# Sheet1.net
KiCad netlist of a schematic drawn in Altium Designer
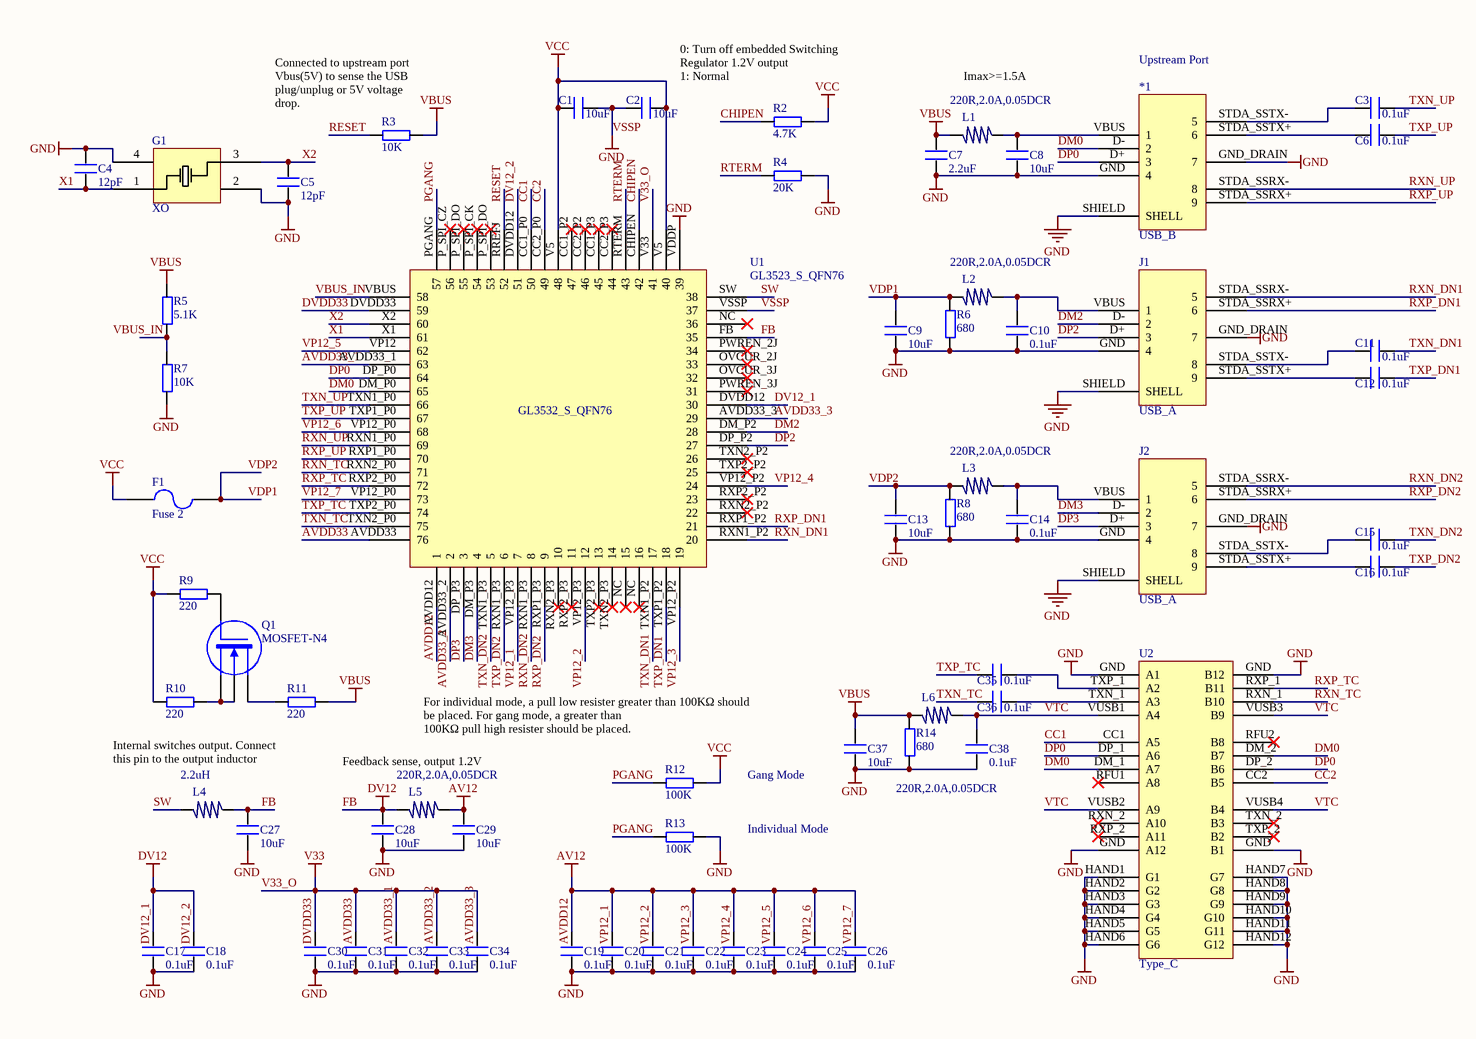
[diagram p0: Sheet1.SchDoc]

(export (version "E")
  (design (tool "Eeschema 10.0.6"))
  (components
    (comp (ref "*1") (value "USB_B") (libsource (lib "GL3532") (part "USB_B")))
    (comp (ref "C1") (value "10uF") (footprint "0603P") (libsource (lib "Explorer STM32F407封装库") (part "C")))
    (comp (ref "C2") (value "10uF") (footprint "0603P") (libsource (lib "Explorer STM32F407封装库") (part "C")))
    (comp (ref "C3") (value "0.1uF") (footprint "0603P") (libsource (lib "Explorer STM32F407封装库") (part "C")))
    (comp (ref "C4") (value "12pF") (footprint "0603P") (libsource (lib "Explorer STM32F407封装库") (part "C")))
    (comp (ref "C5") (value "12pF") (footprint "0603P") (libsource (lib "Explorer STM32F407封装库") (part "C")))
    (comp (ref "C6") (value "0.1uF") (footprint "0603P") (libsource (lib "Explorer STM32F407封装库") (part "C")))
    (comp (ref "C7") (value "2.2uF") (footprint "0603P") (libsource (lib "Explorer STM32F407封装库") (part "C")))
    (comp (ref "C8") (value "10uF") (footprint "0603P") (libsource (lib "Explorer STM32F407封装库") (part "C")))
    (comp (ref "C9") (value "10uF") (footprint "0603P") (libsource (lib "Explorer STM32F407封装库") (part "C")))
    (comp (ref "C10")
      (value "0.1uF")
      (footprint "0603P")
      (libsource (lib "Explorer STM32F407封装库") (part "C"))
    )
    (comp (ref "C11")
      (value "0.1uF")
      (footprint "0603P")
      (libsource (lib "Explorer STM32F407封装库") (part "C"))
    )
    (comp (ref "C12")
      (value "0.1uF")
      (footprint "0603P")
      (libsource (lib "Explorer STM32F407封装库") (part "C"))
    )
    (comp (ref "C13") (value "10uF") (footprint "0603P") (libsource (lib "Explorer STM32F407封装库") (part "C")))
    (comp (ref "C14")
      (value "0.1uF")
      (footprint "0603P")
      (libsource (lib "Explorer STM32F407封装库") (part "C"))
    )
    (comp (ref "C15")
      (value "0.1uF")
      (footprint "0603P")
      (libsource (lib "Explorer STM32F407封装库") (part "C"))
    )
    (comp (ref "C16")
      (value "0.1uF")
      (footprint "0603P")
      (libsource (lib "Explorer STM32F407封装库") (part "C"))
    )
    (comp (ref "C17")
      (value "0.1uF")
      (footprint "0603P")
      (libsource (lib "Explorer STM32F407封装库") (part "C"))
    )
    (comp (ref "C18")
      (value "0.1uF")
      (footprint "0603P")
      (libsource (lib "Explorer STM32F407封装库") (part "C"))
    )
    (comp (ref "C19")
      (value "0.1uF")
      (footprint "0603P")
      (libsource (lib "Explorer STM32F407封装库") (part "C"))
    )
    (comp (ref "C20")
      (value "0.1uF")
      (footprint "0603P")
      (libsource (lib "Explorer STM32F407封装库") (part "C"))
    )
    (comp (ref "C21")
      (value "0.1uF")
      (footprint "0603P")
      (libsource (lib "Explorer STM32F407封装库") (part "C"))
    )
    (comp (ref "C22")
      (value "0.1uF")
      (footprint "0603P")
      (libsource (lib "Explorer STM32F407封装库") (part "C"))
    )
    (comp (ref "C23")
      (value "0.1uF")
      (footprint "0603P")
      (libsource (lib "Explorer STM32F407封装库") (part "C"))
    )
    (comp (ref "C24")
      (value "0.1uF")
      (footprint "0603P")
      (libsource (lib "Explorer STM32F407封装库") (part "C"))
    )
    (comp (ref "C25")
      (value "0.1uF")
      (footprint "0603P")
      (libsource (lib "Explorer STM32F407封装库") (part "C"))
    )
    (comp (ref "C26")
      (value "0.1uF")
      (footprint "0603P")
      (libsource (lib "Explorer STM32F407封装库") (part "C"))
    )
    (comp (ref "C27") (value "10uF") (footprint "0603P") (libsource (lib "Explorer STM32F407封装库") (part "C")))
    (comp (ref "C28") (value "10uF") (footprint "0603P") (libsource (lib "Explorer STM32F407封装库") (part "C")))
    (comp (ref "C29") (value "10uF") (footprint "0603P") (libsource (lib "Explorer STM32F407封装库") (part "C")))
    (comp (ref "C30")
      (value "0.1uF")
      (footprint "0603P")
      (libsource (lib "Explorer STM32F407封装库") (part "C"))
    )
    (comp (ref "C31")
      (value "0.1uF")
      (footprint "0603P")
      (libsource (lib "Explorer STM32F407封装库") (part "C"))
    )
    (comp (ref "C32")
      (value "0.1uF")
      (footprint "0603P")
      (libsource (lib "Explorer STM32F407封装库") (part "C"))
    )
    (comp (ref "C33")
      (value "0.1uF")
      (footprint "0603P")
      (libsource (lib "Explorer STM32F407封装库") (part "C"))
    )
    (comp (ref "C34")
      (value "0.1uF")
      (footprint "0603P")
      (libsource (lib "Explorer STM32F407封装库") (part "C"))
    )
    (comp (ref "C35")
      (value "0.1uF")
      (footprint "0603P")
      (libsource (lib "Explorer STM32F407封装库") (part "C"))
    )
    (comp (ref "C36")
      (value "0.1uF")
      (footprint "0603P")
      (libsource (lib "Explorer STM32F407封装库") (part "C"))
    )
    (comp (ref "C37") (value "10uF") (footprint "0603P") (libsource (lib "Explorer STM32F407封装库") (part "C")))
    (comp (ref "C38")
      (value "0.1uF")
      (footprint "0603P")
      (libsource (lib "Explorer STM32F407封装库") (part "C"))
    )
    (comp (ref "F1")
      (value "Fuse 2")
      (footprint "PIN-W2/E2.8")
      (description "Fuse")
      (fields (field (name "PUBLISHER") "Altium Limited"))
      (libsource (lib "Miscellaneous Devices") (part "Fuse 2"))
    )
    (comp (ref "G1") (value "XO") (description "25M XO") (libsource (lib "GL3532") (part "XO")))
    (comp (ref "J1") (value "USB_A") (description "USB3.0-A") (libsource (lib "GL3532") (part "USB_A")))
    (comp (ref "J2") (value "USB_A") (description "USB3.0-A") (libsource (lib "GL3532") (part "USB_A")))
    (comp (ref "L1")
      (value "220R,2.0A,0.05DCR")
      (footprint "0603P")
      (libsource (lib "Explorer STM32F407封装库") (part "L"))
    )
    (comp (ref "L2")
      (value "220R,2.0A,0.05DCR")
      (footprint "0603P")
      (libsource (lib "Explorer STM32F407封装库") (part "L"))
    )
    (comp (ref "L3")
      (value "220R,2.0A,0.05DCR")
      (footprint "0603P")
      (libsource (lib "Explorer STM32F407封装库") (part "L"))
    )
    (comp (ref "L4") (value "2.2uH") (footprint "0603P") (libsource (lib "Explorer STM32F407封装库") (part "L")))
    (comp (ref "L5")
      (value "220R,2.0A,0.05DCR")
      (footprint "0603P")
      (libsource (lib "Explorer STM32F407封装库") (part "L"))
    )
    (comp (ref "L6")
      (value "220R,2.0A,0.05DCR")
      (footprint "0603P")
      (libsource (lib "Explorer STM32F407封装库") (part "L"))
    )
    (comp (ref "Q1")
      (value "MOSFET-N4")
      (footprint "SOT-343_N")
      (description "N-Channel MOSFET, Externally Terminated Substrate")
      (fields (field (name "PUBLISHER") "Altium Limited"))
      (libsource (lib "Miscellaneous Devices") (part "MOSFET-N4"))
    )
    (comp (ref "R2") (value "4.7K") (footprint "0603P") (libsource (lib "Explorer STM32F407封装库") (part "R")))
    (comp (ref "R3") (value "10K") (footprint "0603P") (libsource (lib "Explorer STM32F407封装库") (part "R")))
    (comp (ref "R4") (value "20K") (footprint "0603P") (libsource (lib "Explorer STM32F407封装库") (part "R")))
    (comp (ref "R5") (value "5.1K") (footprint "0603P") (libsource (lib "Explorer STM32F407封装库") (part "R")))
    (comp (ref "R6") (value "680") (footprint "0603P") (libsource (lib "Explorer STM32F407封装库") (part "R")))
    (comp (ref "R7") (value "10K") (footprint "0603P") (libsource (lib "Explorer STM32F407封装库") (part "R")))
    (comp (ref "R8") (value "680") (footprint "0603P") (libsource (lib "Explorer STM32F407封装库") (part "R")))
    (comp (ref "R9") (value "220") (footprint "0603P") (libsource (lib "Explorer STM32F407封装库") (part "R")))
    (comp (ref "R10") (value "220") (footprint "0603P") (libsource (lib "Explorer STM32F407封装库") (part "R")))
    (comp (ref "R11") (value "220") (footprint "0603P") (libsource (lib "Explorer STM32F407封装库") (part "R")))
    (comp (ref "R12") (value "100K") (footprint "0603P") (libsource (lib "Explorer STM32F407封装库") (part "R")))
    (comp (ref "R13") (value "100K") (footprint "0603P") (libsource (lib "Explorer STM32F407封装库") (part "R")))
    (comp (ref "R14") (value "680") (footprint "0603P") (libsource (lib "Explorer STM32F407封装库") (part "R")))
    (comp (ref "U1") (value "GL3523_S_QFN76") (libsource (lib "GL3532") (part "GL3523_S_QFN76")))
    (comp (ref "U2") (value "Type_C") (libsource (lib "GL3532") (part "Type_C")))
  )
  (nets
    (net (code "1") (name "/AVDD12") (class "Default")
      (node (ref "U1") (pin "AVDD12") (pinfunction "1_AVDD12") (pintype "passive"))
    )
    (net (code "2") (name "/AVDD33") (class "Default")
      (node (ref "U1") (pin "AVDD33") (pinfunction "76_AVDD33") (pintype "passive"))
    )
    (net (code "3") (name "/AVDD33_1") (class "Default")
      (node (ref "U1") (pin "AVDD33_1") (pinfunction "63_AVDD33_1") (pintype "passive"))
    )
    (net (code "5") (name "/AVDD33_3") (class "Default")
      (node (ref "U1") (pin "AVDD33_3") (pinfunction "29_AVDD33_3") (pintype "passive"))
    )
    (net (code "6") (name "/CC1") (class "Default")
      (node (ref "U1") (pin "CC1_P0") (pinfunction "50_CC1_P0") (pintype "passive"))
      (node (ref "U2") (pin "CC1") (pinfunction "A5_CC1") (pintype "passive"))
    )
    (net (code "7") (name "/CC2") (class "Default")
      (node (ref "U1") (pin "CC2_P0") (pinfunction "49_CC2_P0") (pintype "passive"))
      (node (ref "U2") (pin "CC2") (pinfunction "B5_CC2") (pintype "passive"))
    )
    (net (code "8") (name "/CHIPEN") (class "Default")
      (node (ref "R2") (pin "1") (pintype "passive"))
      (node (ref "U1") (pin "CHIPEN") (pinfunction "42_CHIPEN") (pintype "passive"))
    )
    (net (code "9") (name "/DM0") (class "Default")
      (node (ref "*1") (pin "D-") (pinfunction "2_D-") (pintype "passive"))
      (node (ref "U1") (pin "DM_P0") (pinfunction "65_DM_P0") (pintype "passive"))
      (node (ref "U2") (pin "DM_1") (pinfunction "A7_DM_1") (pintype "passive"))
      (node (ref "U2") (pin "DM_2") (pinfunction "B7_DM_2") (pintype "passive"))
    )
    (net (code "10") (name "/DM2") (class "Default")
      (node (ref "J1") (pin "D-") (pinfunction "2_D-") (pintype "passive"))
      (node (ref "U1") (pin "DM_P2") (pinfunction "28_DM_P2") (pintype "passive"))
    )
    (net (code "11") (name "/DM3") (class "Default")
      (node (ref "J2") (pin "D-") (pinfunction "2_D-") (pintype "passive"))
      (node (ref "U1") (pin "DM_P3") (pinfunction "4_DM_P3") (pintype "passive"))
    )
    (net (code "12") (name "/DP0") (class "Default")
      (node (ref "*1") (pin "D+") (pinfunction "3_D+") (pintype "passive"))
      (node (ref "U1") (pin "DP_P0") (pinfunction "64_DP_P0") (pintype "passive"))
      (node (ref "U2") (pin "DP_1") (pinfunction "A6_DP_1") (pintype "passive"))
      (node (ref "U2") (pin "DP_2") (pinfunction "B6_DP_2") (pintype "passive"))
    )
    (net (code "13") (name "/DP2") (class "Default")
      (node (ref "J1") (pin "D+") (pinfunction "3_D+") (pintype "passive"))
      (node (ref "U1") (pin "DP_P2") (pinfunction "27_DP_P2") (pintype "passive"))
    )
    (net (code "14") (name "/DP3") (class "Default")
      (node (ref "J2") (pin "D+") (pinfunction "3_D+") (pintype "passive"))
      (node (ref "U1") (pin "DP_P3") (pinfunction "3_DP_P3") (pintype "passive"))
    )
    (net (code "15") (name "/DV12_1") (class "Default")
      (node (ref "U1") (pin "DVDD12") (pinfunction "30_DVDD12") (pintype "passive"))
    )
    (net (code "16") (name "/DV12_2") (class "Default")
      (node (ref "U1") (pin "DVDD12") (pinfunction "51_DVDD12") (pintype "passive"))
    )
    (net (code "17") (name "/DVDD33") (class "Default")
      (node (ref "U1") (pin "DVDD33") (pinfunction "59_DVDD33") (pintype "passive"))
    )
    (net (code "18") (name "/PGANG") (class "Default")
      (node (ref "R12") (pin "1") (pintype "passive"))
      (node (ref "R13") (pin "1") (pintype "passive"))
      (node (ref "U1") (pin "PGANG") (pinfunction "57_PGANG") (pintype "passive"))
    )
    (net (code "19") (name "/RESET") (class "Default")
      (node (ref "R3") (pin "1") (pintype "passive"))
      (node (ref "U1") (pin "RREFJ") (pinfunction "52_RREFJ") (pintype "passive"))
    )
    (net (code "20") (name "/RTERM") (class "Default")
      (node (ref "R4") (pin "1") (pintype "passive"))
      (node (ref "U1") (pin "RTERM") (pinfunction "43_RTERM") (pintype "passive"))
    )
    (net (code "21") (name "/RXN_DN1") (class "Default")
      (node (ref "J1") (pin "STDA_SSRX-") (pinfunction "5_STDA_SSRX-") (pintype "passive"))
      (node (ref "U1") (pin "RXN1_P2") (pinfunction "20_RXN1_P2") (pintype "passive"))
    )
    (net (code "22") (name "/RXN_DN2") (class "Default")
      (node (ref "J2") (pin "STDA_SSRX-") (pinfunction "5_STDA_SSRX-") (pintype "passive"))
    )
    (net (code "23") (name "/RXN_TC") (class "Default")
      (node (ref "U1") (pin "RXN2_P0") (pinfunction "71_RXN2_P0") (pintype "passive"))
      (node (ref "U2") (pin "RXN_1") (pinfunction "B10_RXN_1") (pintype "passive"))
    )
    (net (code "24") (name "/RXN_UP") (class "Default")
      (node (ref "*1") (pin "STDA_SSRX-") (pinfunction "8_STDA_SSRX-") (pintype "passive"))
      (node (ref "U1") (pin "RXN1_P0") (pinfunction "69_RXN1_P0") (pintype "passive"))
    )
    (net (code "25") (name "/RXP_DN1") (class "Default")
      (node (ref "J1") (pin "STDA_SSRX+") (pinfunction "6_STDA_SSRX+") (pintype "passive"))
      (node (ref "U1") (pin "RXP1_P2") (pinfunction "21_RXP1_P2") (pintype "passive"))
    )
    (net (code "26") (name "/RXP_DN2") (class "Default")
      (node (ref "J2") (pin "STDA_SSRX+") (pinfunction "6_STDA_SSRX+") (pintype "passive"))
    )
    (net (code "27") (name "/RXP_TC") (class "Default")
      (node (ref "U1") (pin "RXP2_P0") (pinfunction "72_RXP2_P0") (pintype "passive"))
      (node (ref "U2") (pin "RXP_1") (pinfunction "B11_RXP_1") (pintype "passive"))
    )
    (net (code "28") (name "/RXP_UP") (class "Default")
      (node (ref "*1") (pin "STDA_SSRX+") (pinfunction "9_STDA_SSRX+") (pintype "passive"))
      (node (ref "U1") (pin "RXP1_P0") (pinfunction "70_RXP1_P0") (pintype "passive"))
    )
    (net (code "29") (name "/SW") (class "Default")
      (node (ref "L4") (pin "2") (pintype "passive"))
      (node (ref "U1") (pin "SW") (pinfunction "38_SW") (pintype "passive"))
    )
    (net (code "30") (name "/TXN_DN1") (class "Default") (node (ref "C11") (pin "2") (pintype "passive")))
    (net (code "31") (name "/TXN_DN2") (class "Default") (node (ref "C15") (pin "2") (pintype "passive")))
    (net (code "32") (name "/TXN_TC") (class "Default")
      (node (ref "C36") (pin "1") (pintype "passive"))
      (node (ref "U1") (pin "TXN2_P0") (pinfunction "75_TXN2_P0") (pintype "passive"))
    )
    (net (code "33") (name "/TXN_UP") (class "Default")
      (node (ref "C3") (pin "2") (pintype "passive"))
      (node (ref "U1") (pin "TXN1_P0") (pinfunction "66_TXN1_P0") (pintype "passive"))
    )
    (net (code "34") (name "/TXP_DN1") (class "Default") (node (ref "C12") (pin "2") (pintype "passive")))
    (net (code "35") (name "/TXP_DN2") (class "Default") (node (ref "C16") (pin "2") (pintype "passive")))
    (net (code "36") (name "/TXP_TC") (class "Default")
      (node (ref "C35") (pin "1") (pintype "passive"))
      (node (ref "U1") (pin "TXP2_P0") (pinfunction "74_TXP2_P0") (pintype "passive"))
    )
    (net (code "37") (name "/TXP_UP") (class "Default")
      (node (ref "C6") (pin "2") (pintype "passive"))
      (node (ref "U1") (pin "TXP1_P0") (pinfunction "67_TXP1_P0") (pintype "passive"))
    )
    (net (code "38") (name "/VBUS_IN") (class "Default")
      (node (ref "U1") (pin "VBUS") (pinfunction "58_VBUS") (pintype "passive"))
    )
    (net (code "39") (name "/VDP1") (class "Default")
      (node (ref "C13") (pin "2") (pintype "passive"))
      (node (ref "C9") (pin "2") (pintype "passive"))
      (node (ref "F1") (pin "2") (pinfunction "2_2") (pintype "passive"))
      (node (ref "L2") (pin "2") (pintype "passive"))
      (node (ref "L3") (pin "2") (pintype "passive"))
      (node (ref "R6") (pin "2") (pintype "passive"))
      (node (ref "R8") (pin "2") (pintype "passive"))
    )
    (net (code "43") (name "/VP12_4") (class "Default")
      (node (ref "U1") (pin "VP12_P2") (pinfunction "24_VP12_P2") (pintype "passive"))
    )
    (net (code "44") (name "/VP12_5") (class "Default")
      (node (ref "U1") (pin "VP12") (pinfunction "62_VP12") (pintype "passive"))
    )
    (net (code "45") (name "/VP12_6") (class "Default")
      (node (ref "U1") (pin "VP12_P0") (pinfunction "68_VP12_P0") (pintype "passive"))
    )
    (net (code "46") (name "/VP12_7") (class "Default")
      (node (ref "U1") (pin "VP12_P0") (pinfunction "73_VP12_P0") (pintype "passive"))
    )
    (net (code "47") (name "/VTC") (class "Default")
      (node (ref "C38") (pin "2") (pintype "passive"))
      (node (ref "L6") (pin "1") (pintype "passive"))
      (node (ref "U2") (pin "VUSB1") (pinfunction "A4_VUSB1") (pintype "passive"))
      (node (ref "U2") (pin "VUSB2") (pinfunction "A9_VUSB2") (pintype "passive"))
      (node (ref "U2") (pin "VUSB3") (pinfunction "B9_VUSB3") (pintype "passive"))
      (node (ref "U2") (pin "VUSB4") (pinfunction "B4_VUSB4") (pintype "passive"))
    )
    (net (code "48") (name "/X1") (class "Default")
      (node (ref "C4") (pin "1") (pintype "passive"))
      (node (ref "G1") (pin "1") (pintype "passive"))
      (node (ref "U1") (pin "X1") (pinfunction "61_X1") (pintype "passive"))
    )
    (net (code "49") (name "/X2") (class "Default")
      (node (ref "C5") (pin "2") (pintype "passive"))
      (node (ref "G1") (pin "3") (pintype "passive"))
      (node (ref "U1") (pin "X2") (pinfunction "60_X2") (pintype "passive"))
    )
    (net (code "50") (name "AV12") (class "Default")
      (node (ref "C19") (pin "2") (pintype "passive"))
      (node (ref "C20") (pin "2") (pintype "passive"))
      (node (ref "C21") (pin "2") (pintype "passive"))
      (node (ref "C22") (pin "2") (pintype "passive"))
      (node (ref "C23") (pin "2") (pintype "passive"))
      (node (ref "C24") (pin "2") (pintype "passive"))
      (node (ref "C25") (pin "2") (pintype "passive"))
      (node (ref "C26") (pin "2") (pintype "passive"))
      (node (ref "C29") (pin "2") (pintype "passive"))
      (node (ref "L5") (pin "1") (pintype "passive"))
    )
    (net (code "51") (name "DV12") (class "Default")
      (node (ref "C17") (pin "2") (pintype "passive"))
      (node (ref "C18") (pin "2") (pintype "passive"))
      (node (ref "C27") (pin "2") (pintype "passive"))
      (node (ref "C28") (pin "2") (pintype "passive"))
      (node (ref "L4") (pin "1") (pintype "passive"))
      (node (ref "L5") (pin "2") (pintype "passive"))
      (node (ref "U1") (pin "FB") (pinfunction "35_FB") (pintype "passive"))
    )
    (net (code "52") (name "GND") (class "Default")
      (node (ref "*1") (pin "GND") (pinfunction "4_GND") (pintype "passive"))
      (node (ref "*1") (pin "GND_DRAIN") (pinfunction "7_GND_DRAIN") (pintype "passive"))
      (node (ref "*1") (pin "SHIELD") (pinfunction "SHELL_SHIELD") (pintype "passive"))
      (node (ref "C1") (pin "2") (pintype "passive"))
      (node (ref "C10") (pin "1") (pintype "passive"))
      (node (ref "C13") (pin "1") (pintype "passive"))
      (node (ref "C14") (pin "1") (pintype "passive"))
      (node (ref "C17") (pin "1") (pintype "passive"))
      (node (ref "C18") (pin "1") (pintype "passive"))
      (node (ref "C19") (pin "1") (pintype "passive"))
      (node (ref "C2") (pin "1") (pintype "passive"))
      (node (ref "C20") (pin "1") (pintype "passive"))
      (node (ref "C21") (pin "1") (pintype "passive"))
      (node (ref "C22") (pin "1") (pintype "passive"))
      (node (ref "C23") (pin "1") (pintype "passive"))
      (node (ref "C24") (pin "1") (pintype "passive"))
      (node (ref "C25") (pin "1") (pintype "passive"))
      (node (ref "C26") (pin "1") (pintype "passive"))
      (node (ref "C27") (pin "1") (pintype "passive"))
      (node (ref "C28") (pin "1") (pintype "passive"))
      (node (ref "C29") (pin "1") (pintype "passive"))
      (node (ref "C30") (pin "1") (pintype "passive"))
      (node (ref "C31") (pin "1") (pintype "passive"))
      (node (ref "C32") (pin "1") (pintype "passive"))
      (node (ref "C33") (pin "1") (pintype "passive"))
      (node (ref "C34") (pin "1") (pintype "passive"))
      (node (ref "C37") (pin "1") (pintype "passive"))
      (node (ref "C38") (pin "1") (pintype "passive"))
      (node (ref "C4") (pin "2") (pintype "passive"))
      (node (ref "C5") (pin "1") (pintype "passive"))
      (node (ref "C7") (pin "1") (pintype "passive"))
      (node (ref "C8") (pin "1") (pintype "passive"))
      (node (ref "C9") (pin "1") (pintype "passive"))
      (node (ref "G1") (pin "2") (pintype "passive"))
      (node (ref "G1") (pin "4") (pintype "passive"))
      (node (ref "J1") (pin "GND") (pinfunction "4_GND") (pintype "passive"))
      (node (ref "J1") (pin "GND_DRAIN") (pinfunction "7_GND_DRAIN") (pintype "passive"))
      (node (ref "J1") (pin "SHIELD") (pinfunction "SHELL_SHIELD") (pintype "passive"))
      (node (ref "J2") (pin "GND") (pinfunction "4_GND") (pintype "passive"))
      (node (ref "J2") (pin "GND_DRAIN") (pinfunction "7_GND_DRAIN") (pintype "passive"))
      (node (ref "J2") (pin "SHIELD") (pinfunction "SHELL_SHIELD") (pintype "passive"))
      (node (ref "R13") (pin "2") (pintype "passive"))
      (node (ref "R14") (pin "1") (pintype "passive"))
      (node (ref "R4") (pin "2") (pintype "passive"))
      (node (ref "R6") (pin "1") (pintype "passive"))
      (node (ref "R7") (pin "1") (pintype "passive"))
      (node (ref "R8") (pin "1") (pintype "passive"))
      (node (ref "U1") (pin "VDDP") (pinfunction "39_VDDP") (pintype "passive"))
      (node (ref "U1") (pin "VSSP") (pinfunction "37_VSSP") (pintype "passive"))
      (node (ref "U2") (pin "GND") (pinfunction "B1_GND") (pintype "passive"))
      (node (ref "U2") (pin "HAND1") (pinfunction "G1_HAND1") (pintype "passive"))
      (node (ref "U2") (pin "HAND10") (pinfunction "G10_HAND10") (pintype "passive"))
      (node (ref "U2") (pin "HAND11") (pinfunction "G11_HAND11") (pintype "passive"))
      (node (ref "U2") (pin "HAND12") (pinfunction "G12_HAND12") (pintype "passive"))
      (node (ref "U2") (pin "HAND2") (pinfunction "G2_HAND2") (pintype "passive"))
      (node (ref "U2") (pin "HAND3") (pinfunction "G3_HAND3") (pintype "passive"))
      (node (ref "U2") (pin "HAND4") (pinfunction "G4_HAND4") (pintype "passive"))
      (node (ref "U2") (pin "HAND5") (pinfunction "G5_HAND5") (pintype "passive"))
      (node (ref "U2") (pin "HAND6") (pinfunction "G6_HAND6") (pintype "passive"))
      (node (ref "U2") (pin "HAND7") (pinfunction "G7_HAND7") (pintype "passive"))
      (node (ref "U2") (pin "HAND8") (pinfunction "G8_HAND8") (pintype "passive"))
      (node (ref "U2") (pin "HAND9") (pinfunction "G9_HAND9") (pintype "passive"))
    )
    (net (code "53") (name "Net-(*1-1)") (class "Default")
      (node (ref "*1") (pin "VBUS") (pinfunction "1_VBUS") (pintype "passive"))
      (node (ref "C8") (pin "2") (pintype "passive"))
      (node (ref "L1") (pin "1") (pintype "passive"))
    )
    (net (code "54") (name "Net-(*1-5)") (class "Default")
      (node (ref "*1") (pin "STDA_SSTX-") (pinfunction "5_STDA_SSTX-") (pintype "passive"))
      (node (ref "C3") (pin "1") (pintype "passive"))
    )
    (net (code "55") (name "Net-(*1-6)") (class "Default")
      (node (ref "*1") (pin "STDA_SSTX+") (pinfunction "6_STDA_SSTX+") (pintype "passive"))
      (node (ref "C6") (pin "1") (pintype "passive"))
    )
    (net (code "56") (name "Net-(J1-1)") (class "Default")
      (node (ref "C10") (pin "2") (pintype "passive"))
      (node (ref "J1") (pin "VBUS") (pinfunction "1_VBUS") (pintype "passive"))
      (node (ref "L2") (pin "1") (pintype "passive"))
    )
    (net (code "57") (name "Net-(J1-8)") (class "Default")
      (node (ref "C11") (pin "1") (pintype "passive"))
      (node (ref "J1") (pin "STDA_SSTX-") (pinfunction "8_STDA_SSTX-") (pintype "passive"))
    )
    (net (code "58") (name "Net-(J1-9)") (class "Default")
      (node (ref "C12") (pin "1") (pintype "passive"))
      (node (ref "J1") (pin "STDA_SSTX+") (pinfunction "9_STDA_SSTX+") (pintype "passive"))
    )
    (net (code "59") (name "Net-(J2-1)") (class "Default")
      (node (ref "C14") (pin "2") (pintype "passive"))
      (node (ref "J2") (pin "VBUS") (pinfunction "1_VBUS") (pintype "passive"))
      (node (ref "L3") (pin "1") (pintype "passive"))
    )
    (net (code "60") (name "Net-(J2-8)") (class "Default")
      (node (ref "C15") (pin "1") (pintype "passive"))
      (node (ref "J2") (pin "STDA_SSTX-") (pinfunction "8_STDA_SSTX-") (pintype "passive"))
    )
    (net (code "61") (name "Net-(J2-9)") (class "Default")
      (node (ref "C16") (pin "1") (pintype "passive"))
      (node (ref "J2") (pin "STDA_SSTX+") (pinfunction "9_STDA_SSTX+") (pintype "passive"))
    )
    (net (code "62") (name "Net-(Q1-D)") (class "Default")
      (node (ref "Q1") (pin "2") (pinfunction "D_2") (pintype "passive"))
      (node (ref "R11") (pin "1") (pintype "passive"))
    )
    (net (code "63") (name "Net-(Q1-G)") (class "Default")
      (node (ref "Q1") (pin "1") (pinfunction "G_1") (pintype "passive"))
      (node (ref "R9") (pin "2") (pintype "passive"))
    )
    (net (code "64") (name "Net-(Q1-S)") (class "Default")
      (node (ref "Q1") (pin "3") (pinfunction "U_3") (pintype "passive"))
      (node (ref "Q1") (pin "4") (pinfunction "S_4") (pintype "passive"))
      (node (ref "R10") (pin "2") (pintype "passive"))
    )
    (net (code "65") (name "Net-(R5-Pad1)") (class "Default")
      (node (ref "R5") (pin "1") (pintype "passive"))
      (node (ref "R7") (pin "2") (pintype "passive"))
    )
    (net (code "66") (name "Net-(U2-A2)") (class "Default")
      (node (ref "C35") (pin "2") (pintype "passive"))
      (node (ref "U2") (pin "TXP_1") (pinfunction "A2_TXP_1") (pintype "passive"))
    )
    (net (code "67") (name "Net-(U2-A3)") (class "Default")
      (node (ref "C36") (pin "2") (pintype "passive"))
      (node (ref "U2") (pin "TXN_1") (pinfunction "A3_TXN_1") (pintype "passive"))
    )
    (net (code "68") (name "V33") (class "Default")
      (node (ref "C30") (pin "2") (pintype "passive"))
      (node (ref "C31") (pin "2") (pintype "passive"))
      (node (ref "C32") (pin "2") (pintype "passive"))
      (node (ref "C33") (pin "2") (pintype "passive"))
      (node (ref "C34") (pin "2") (pintype "passive"))
      (node (ref "U1") (pin "V33") (pinfunction "41_V33") (pintype "passive"))
    )
    (net (code "69") (name "VBUS") (class "Default")
      (node (ref "C37") (pin "2") (pintype "passive"))
      (node (ref "C7") (pin "2") (pintype "passive"))
      (node (ref "L1") (pin "2") (pintype "passive"))
      (node (ref "L6") (pin "2") (pintype "passive"))
      (node (ref "R11") (pin "2") (pintype "passive"))
      (node (ref "R14") (pin "2") (pintype "passive"))
      (node (ref "R3") (pin "2") (pintype "passive"))
      (node (ref "R5") (pin "2") (pintype "passive"))
    )
    (net (code "70") (name "VCC") (class "Default")
      (node (ref "C1") (pin "1") (pintype "passive"))
      (node (ref "C2") (pin "2") (pintype "passive"))
      (node (ref "F1") (pin "1") (pinfunction "1_1") (pintype "passive"))
      (node (ref "R10") (pin "1") (pintype "passive"))
      (node (ref "R12") (pin "2") (pintype "passive"))
      (node (ref "R2") (pin "2") (pintype "passive"))
      (node (ref "R9") (pin "1") (pintype "passive"))
      (node (ref "U1") (pin "V5") (pinfunction "48_V5") (pintype "passive"))
    )
    (net (code "71") (name "unconnected-(U1-2-PadAVDD33_2)") (class "Default")
      (node (ref "U1") (pin "AVDD33_2") (pinfunction "2_AVDD33_2") (pintype "passive"))
    )
    (net (code "72") (name "unconnected-(U1-5-PadTXN1_P3)") (class "Default")
      (node (ref "U1") (pin "TXN1_P3") (pinfunction "5_TXN1_P3") (pintype "passive"))
    )
    (net (code "73") (name "unconnected-(U1-6-PadRXN1_P3)") (class "Default")
      (node (ref "U1") (pin "RXN1_P3") (pinfunction "6_RXN1_P3") (pintype "passive"))
    )
    (net (code "74") (name "unconnected-(U1-7-PadVP12_P3)") (class "Default")
      (node (ref "U1") (pin "VP12_P3") (pinfunction "7_VP12_P3") (pintype "passive"))
    )
    (net (code "75") (name "unconnected-(U1-8-PadRXN1_P3)") (class "Default")
      (node (ref "U1") (pin "RXN1_P3") (pinfunction "8_RXN1_P3") (pintype "passive"))
    )
    (net (code "76") (name "unconnected-(U1-9-PadRXP1_P3)") (class "Default")
      (node (ref "U1") (pin "RXP1_P3") (pinfunction "9_RXP1_P3") (pintype "passive"))
    )
    (net (code "77") (name "unconnected-(U1-10-PadRXN2_P3)") (class "Default")
      (node (ref "U1") (pin "RXN2_P3") (pinfunction "10_RXN2_P3") (pintype "passive+no_connect"))
    )
    (net (code "78") (name "unconnected-(U1-11-PadRXP2_P3)") (class "Default")
      (node (ref "U1") (pin "RXP2_P3") (pinfunction "11_RXP2_P3") (pintype "passive+no_connect"))
    )
    (net (code "79") (name "unconnected-(U1-12-PadVP12_P3)") (class "Default")
      (node (ref "U1") (pin "VP12_P3") (pinfunction "12_VP12_P3") (pintype "passive"))
    )
    (net (code "80") (name "unconnected-(U1-13-PadTXP2_P3)") (class "Default")
      (node (ref "U1") (pin "TXP2_P3") (pinfunction "13_TXP2_P3") (pintype "passive+no_connect"))
    )
    (net (code "81") (name "unconnected-(U1-14-PadTXN2_P3)") (class "Default")
      (node (ref "U1") (pin "TXN2_P3") (pinfunction "14_TXN2_P3") (pintype "passive+no_connect"))
    )
    (net (code "82") (name "unconnected-(U1-15-PadNC)") (class "Default")
      (node (ref "U1") (pin "NC") (pinfunction "15_NC") (pintype "passive+no_connect"))
    )
    (net (code "83") (name "unconnected-(U1-16-PadNC)") (class "Default")
      (node (ref "U1") (pin "NC") (pinfunction "16_NC") (pintype "passive+no_connect"))
    )
    (net (code "84") (name "unconnected-(U1-17-PadTXN1_P2)") (class "Default")
      (node (ref "U1") (pin "TXN1_P2") (pinfunction "17_TXN1_P2") (pintype "passive"))
    )
    (net (code "85") (name "unconnected-(U1-18-PadTXP1_P2)") (class "Default")
      (node (ref "U1") (pin "TXP1_P2") (pinfunction "18_TXP1_P2") (pintype "passive"))
    )
    (net (code "86") (name "unconnected-(U1-19-PadVP12_P2)") (class "Default")
      (node (ref "U1") (pin "VP12_P2") (pinfunction "19_VP12_P2") (pintype "passive"))
    )
    (net (code "87") (name "unconnected-(U1-22-PadRXN2_P2)") (class "Default")
      (node (ref "U1") (pin "RXN2_P2") (pinfunction "22_RXN2_P2") (pintype "passive+no_connect"))
    )
    (net (code "88") (name "unconnected-(U1-23-PadRXP2_P2)") (class "Default")
      (node (ref "U1") (pin "RXP2_P2") (pinfunction "23_RXP2_P2") (pintype "passive+no_connect"))
    )
    (net (code "89") (name "unconnected-(U1-25-PadTXP2_P2)") (class "Default")
      (node (ref "U1") (pin "TXP2_P2") (pinfunction "25_TXP2_P2") (pintype "passive+no_connect"))
    )
    (net (code "90") (name "unconnected-(U1-26-PadTXN2_P2)") (class "Default")
      (node (ref "U1") (pin "TXN2_P2") (pinfunction "26_TXN2_P2") (pintype "passive+no_connect"))
    )
    (net (code "91") (name "unconnected-(U1-31-PadPWREN_3J)") (class "Default")
      (node (ref "U1") (pin "PWREN_3J") (pinfunction "31_PWREN_3J") (pintype "passive+no_connect"))
    )
    (net (code "92") (name "unconnected-(U1-32-PadOVCUR_3J)") (class "Default")
      (node (ref "U1") (pin "OVCUR_3J") (pinfunction "32_OVCUR_3J") (pintype "passive+no_connect"))
    )
    (net (code "93") (name "unconnected-(U1-33-PadOVCUR_2J)") (class "Default")
      (node (ref "U1") (pin "OVCUR_2J") (pinfunction "33_OVCUR_2J") (pintype "passive+no_connect"))
    )
    (net (code "94") (name "unconnected-(U1-34-PadPWREN_2J)") (class "Default")
      (node (ref "U1") (pin "PWREN_2J") (pinfunction "34_PWREN_2J") (pintype "passive+no_connect"))
    )
    (net (code "95") (name "unconnected-(U1-36-PadNC)") (class "Default")
      (node (ref "U1") (pin "NC") (pinfunction "36_NC") (pintype "passive+no_connect"))
    )
    (net (code "96") (name "unconnected-(U1-44-PadCC2_P3)") (class "Default")
      (node (ref "U1") (pin "CC2_P3") (pinfunction "44_CC2_P3") (pintype "passive+no_connect"))
    )
    (net (code "97") (name "unconnected-(U1-45-PadCC1_P3)") (class "Default")
      (node (ref "U1") (pin "CC1_P3") (pinfunction "45_CC1_P3") (pintype "passive+no_connect"))
    )
    (net (code "98") (name "unconnected-(U1-46-PadCC2_P2)") (class "Default")
      (node (ref "U1") (pin "CC2_P2") (pinfunction "46_CC2_P2") (pintype "passive+no_connect"))
    )
    (net (code "99") (name "unconnected-(U1-47-PadCC1_P2)") (class "Default")
      (node (ref "U1") (pin "CC1_P2") (pinfunction "47_CC1_P2") (pintype "passive+no_connect"))
    )
    (net (code "100") (name "unconnected-(U1-53-PadP_SPI_DO)") (class "Default")
      (node (ref "U1") (pin "P_SPI_DO") (pinfunction "53_P_SPI_DO") (pintype "passive+no_connect"))
    )
    (net (code "101") (name "unconnected-(U1-54-PadP_SPI_CK)") (class "Default")
      (node (ref "U1") (pin "P_SPI_CK") (pinfunction "54_P_SPI_CK") (pintype "passive+no_connect"))
    )
    (net (code "102") (name "unconnected-(U1-55-PadP_SPI_DO)") (class "Default")
      (node (ref "U1") (pin "P_SPI_DO") (pinfunction "55_P_SPI_DO") (pintype "passive+no_connect"))
    )
    (net (code "103") (name "unconnected-(U1-56-PadP_SPI_CZ)") (class "Default")
      (node (ref "U1") (pin "P_SPI_CZ") (pinfunction "56_P_SPI_CZ") (pintype "passive+no_connect"))
    )
    (net (code "104") (name "unconnected-(U2-A8-PadRFU1)") (class "Default")
      (node (ref "U2") (pin "RFU1") (pinfunction "A8_RFU1") (pintype "passive+no_connect"))
    )
    (net (code "105") (name "unconnected-(U2-A10-PadRXN_2)") (class "Default")
      (node (ref "U2") (pin "RXN_2") (pinfunction "A10_RXN_2") (pintype "passive+no_connect"))
    )
    (net (code "106") (name "unconnected-(U2-A11-PadRXP_2)") (class "Default")
      (node (ref "U2") (pin "RXP_2") (pinfunction "A11_RXP_2") (pintype "passive+no_connect"))
    )
    (net (code "107") (name "unconnected-(U2-B2-PadTXP_2)") (class "Default")
      (node (ref "U2") (pin "TXP_2") (pinfunction "B2_TXP_2") (pintype "passive+no_connect"))
    )
    (net (code "108") (name "unconnected-(U2-B3-PadTXN_2)") (class "Default")
      (node (ref "U2") (pin "TXN_2") (pinfunction "B3_TXN_2") (pintype "passive+no_connect"))
    )
    (net (code "109") (name "unconnected-(U2-B8-PadRFU2)") (class "Default")
      (node (ref "U2") (pin "RFU2") (pinfunction "B8_RFU2") (pintype "passive+no_connect"))
    )
  )
)
